# schematic.net
KiCad netlist of a schematic drawn in EAGLE
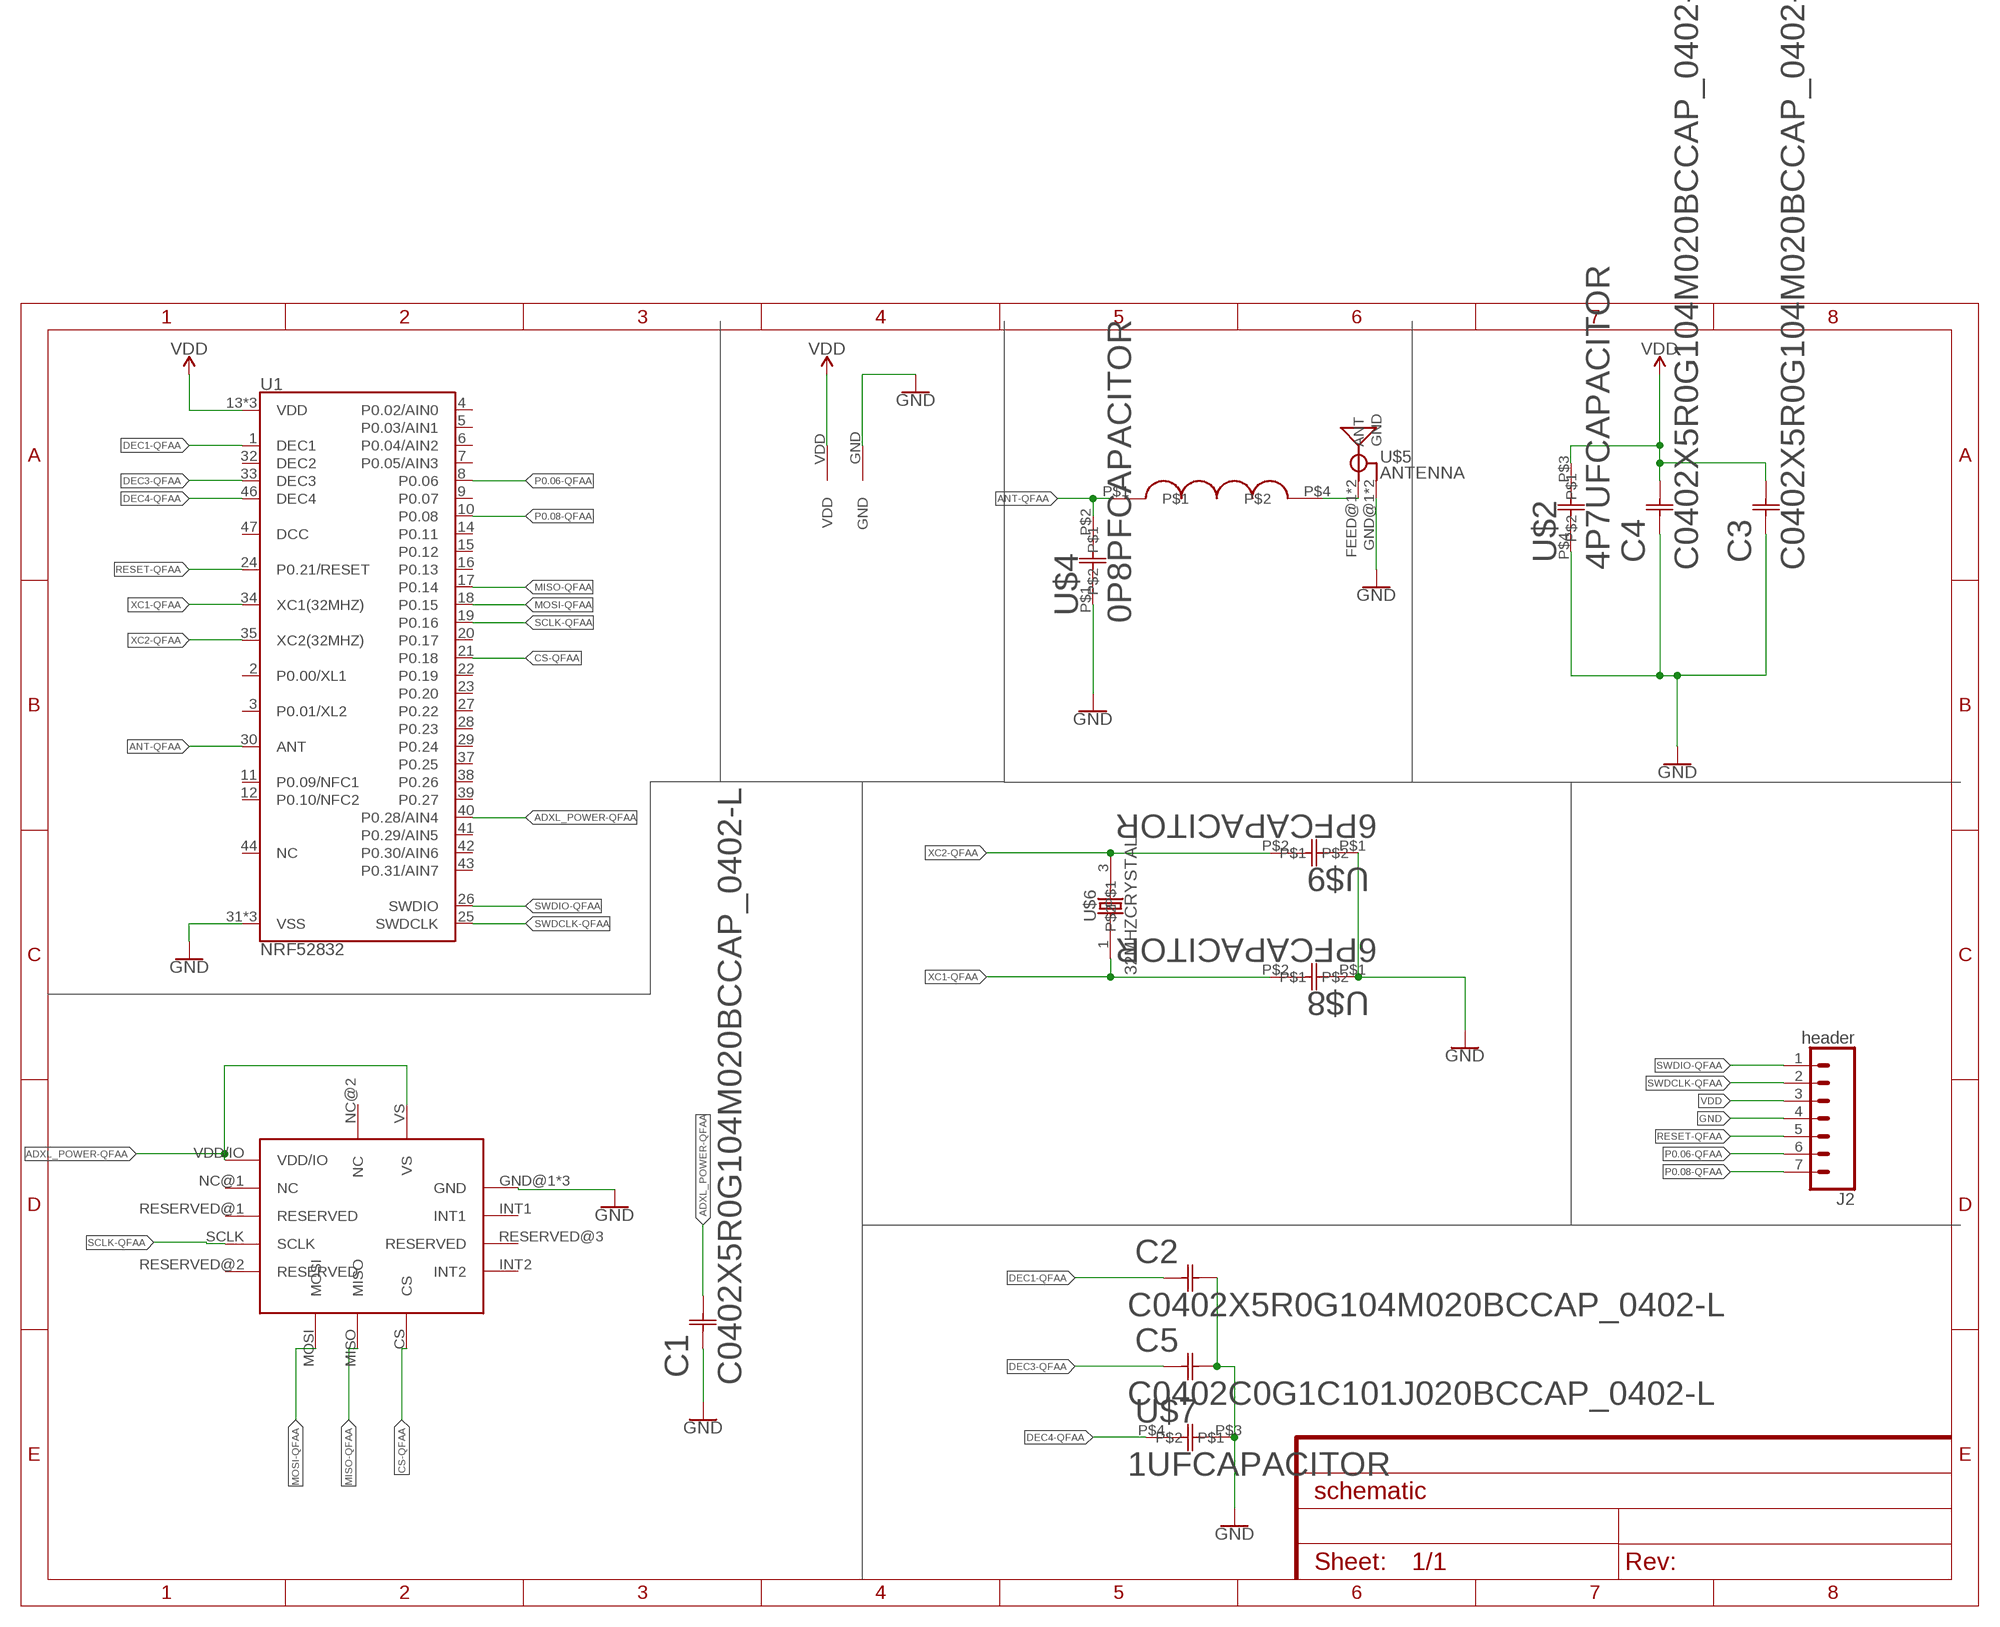
[diagram p0: schematic, sheet 1]

(export (version "E")
  (design (tool "Eeschema 10.0.6"))
  (components
    (comp (ref "C1")
      (value "C0402X5R0G104M020BCCAP_0402-L")
      (footprint "eagle-import:CAP_0402-L")
      (fields (field (name "MANUFACTURER_PART_NUMBER") "C0402C0G1C101J020BC"))
      (libsource (lib "eagle-import") (part "C0402X5R0G104M020BCCAP_0402-L"))
    )
    (comp (ref "C2")
      (value "C0402X5R0G104M020BCCAP_0402-L")
      (footprint "eagle-import:CAP_0402-L")
      (fields (field (name "MANUFACTURER_PART_NUMBER") "C0402C0G1C101J020BC"))
      (libsource (lib "eagle-import") (part "C0402X5R0G104M020BCCAP_0402-L"))
    )
    (comp (ref "C3")
      (value "C0402X5R0G104M020BCCAP_0402-L")
      (footprint "eagle-import:CAP_0402-L")
      (fields (field (name "MANUFACTURER_PART_NUMBER") "C0402C0G1C101J020BC"))
      (libsource (lib "eagle-import") (part "C0402X5R0G104M020BCCAP_0402-L"))
    )
    (comp (ref "C4")
      (value "C0402X5R0G104M020BCCAP_0402-L")
      (footprint "eagle-import:CAP_0402-L")
      (fields (field (name "MANUFACTURER_PART_NUMBER") "C0402C0G1C101J020BC"))
      (libsource (lib "eagle-import") (part "C0402X5R0G104M020BCCAP_0402-L"))
    )
    (comp (ref "C5")
      (value "C0402C0G1C101J020BCCAP_0402-L")
      (footprint "eagle-import:CAP_0402-L")
      (fields (field (name "MANUFACTURER_PART_NUMBER") "C0402C0G1C101J020BC"))
      (libsource (lib "eagle-import") (part "C0402C0G1C101J020BCCAP_0402-L"))
    )
    (comp (ref "J2")
      (value "header")
      (footprint "eagle-import:1X07")
      (libsource (lib "eagle-import") (part "CONN_07"))
    )
    (comp (ref "U$1")
      (value "ADXL362")
      (footprint "eagle-import:TFLGA-16_3.3MMX3.1MM")
      (libsource (lib "eagle-import") (part "ADXL362"))
    )
    (comp (ref "U$2")
      (value "4P7UFCAPACITOR")
      (footprint "eagle-import:4P7UFCAPACITOR")
      (libsource (lib "eagle-import") (part "4P7UFCAPACITOR"))
    )
    (comp (ref "U$3")
      (value "3.9INDUCTOR")
      (footprint "eagle-import:744917039")
      (libsource (lib "eagle-import") (part "3.9INDUCTOR"))
    )
    (comp (ref "U$4")
      (value "0P8PFCAPACITOR")
      (footprint "eagle-import:0P8PFCAPACITOR")
      (libsource (lib "eagle-import") (part "0P8PFCAPACITOR"))
    )
    (comp (ref "U$5")
      (value "ANTENNA")
      (footprint "eagle-import:ANTENNA_FOOTPRINT")
      (libsource (lib "eagle-import") (part "ANTENNA"))
    )
    (comp (ref "U$6")
      (value "32MHZCRYSTAL")
      (footprint "eagle-import:32MHZCRYSTAL")
      (libsource (lib "eagle-import") (part "32MHZCRYSTAL"))
    )
    (comp (ref "U$7")
      (value "1UFCAPACITOR")
      (footprint "eagle-import:1UFCAPACITOR")
      (libsource (lib "eagle-import") (part "1UFCAPACITOR"))
    )
    (comp (ref "U$8")
      (value "6PFCAPACITOR")
      (footprint "eagle-import:6PFCAPACITOR")
      (libsource (lib "eagle-import") (part "6PFCAPACITOR"))
    )
    (comp (ref "U$9")
      (value "6PFCAPACITOR")
      (footprint "eagle-import:6PFCAPACITOR")
      (libsource (lib "eagle-import") (part "6PFCAPACITOR"))
    )
    (comp (ref "U$10")
      (value "POWER")
      (footprint "eagle-import:POWER")
      (libsource (lib "eagle-import") (part "POWER"))
    )
    (comp (ref "U1")
      (value "NRF52832")
      (footprint "eagle-import:QFN48-6X6MM")
      (libsource (lib "eagle-import") (part "NRF52832"))
    )
  )
  (nets
    (net (code "1") (name "ADXL_POWER-QFAA") (class "Default")
      (node (ref "C1") (pin "2") (pinfunction "22_2") (pintype "passive"))
      (node (ref "U$1") (pin "VDD/IO") (pinfunction "VDD/IO_VDD/IO") (pintype "bidirectional"))
      (node (ref "U$1") (pin "VS") (pinfunction "VS_VS") (pintype "bidirectional"))
      (node (ref "U1") (pin "40") (pinfunction "P0.28/AIN4_40") (pintype "bidirectional"))
    )
    (net (code "2") (name "ANT-QFAA") (class "Default")
      (node (ref "U$3") (pin "P$1") (pinfunction "P$1_P$1") (pintype "bidirectional"))
      (node (ref "U$4") (pin "P$2") (pinfunction "P$2_P$2") (pintype "bidirectional"))
      (node (ref "U1") (pin "30") (pinfunction "ANT_30") (pintype "bidirectional"))
    )
    (net (code "3") (name "CS-QFAA") (class "Default")
      (node (ref "U$1") (pin "CS") (pinfunction "CS_CS") (pintype "bidirectional"))
      (node (ref "U1") (pin "21") (pinfunction "P0.18_21") (pintype "bidirectional"))
    )
    (net (code "4") (name "DEC1-QFAA") (class "Default")
      (node (ref "C2") (pin "1") (pinfunction "11_1") (pintype "passive"))
      (node (ref "U1") (pin "1") (pinfunction "DEC1_1") (pintype "bidirectional"))
    )
    (net (code "5") (name "DEC3-QFAA") (class "Default")
      (node (ref "C5") (pin "1") (pinfunction "11_1") (pintype "passive"))
      (node (ref "U1") (pin "33") (pinfunction "DEC3_33") (pintype "bidirectional"))
    )
    (net (code "6") (name "DEC4-QFAA") (class "Default")
      (node (ref "U$7") (pin "P$4") (pinfunction "P$1_P$4") (pintype "bidirectional"))
      (node (ref "U1") (pin "46") (pinfunction "DEC4_46") (pintype "bidirectional"))
    )
    (net (code "7") (name "GND") (class "Default")
      (node (ref "C1") (pin "1") (pinfunction "11_1") (pintype "passive"))
      (node (ref "C2") (pin "2") (pinfunction "22_2") (pintype "passive"))
      (node (ref "C3") (pin "1") (pinfunction "11_1") (pintype "passive"))
      (node (ref "C4") (pin "1") (pinfunction "11_1") (pintype "passive"))
      (node (ref "C5") (pin "2") (pinfunction "22_2") (pintype "passive"))
      (node (ref "J2") (pin "4") (pinfunction "4_4") (pintype "passive"))
      (node (ref "U$1") (pin "GND@1") (pinfunction "GND_GND@1") (pintype "bidirectional"))
      (node (ref "U$1") (pin "GND@2") (pinfunction "GND_GND@2") (pintype "bidirectional"))
      (node (ref "U$1") (pin "GND@3") (pinfunction "GND_GND@3") (pintype "bidirectional"))
      (node (ref "U$10") (pin "GND") (pinfunction "GND_GND") (pintype "bidirectional"))
      (node (ref "U$2") (pin "P$4") (pinfunction "P$1_P$4") (pintype "bidirectional"))
      (node (ref "U$4") (pin "P$1") (pinfunction "P$1_P$1") (pintype "bidirectional"))
      (node (ref "U$5") (pin "GND@1") (pinfunction "GND_GND@1") (pintype "bidirectional"))
      (node (ref "U$5") (pin "GND@2") (pinfunction "GND_GND@2") (pintype "bidirectional"))
      (node (ref "U$7") (pin "P$3") (pinfunction "P$2_P$3") (pintype "bidirectional"))
      (node (ref "U$8") (pin "P$1") (pinfunction "P$1_P$1") (pintype "bidirectional"))
      (node (ref "U$9") (pin "P$1") (pinfunction "P$1_P$1") (pintype "bidirectional"))
      (node (ref "U1") (pin "31") (pinfunction "VSS_31") (pintype "bidirectional"))
      (node (ref "U1") (pin "45") (pinfunction "VSS_45") (pintype "bidirectional"))
      (node (ref "U1") (pin "EP") (pinfunction "VSS_EP") (pintype "bidirectional"))
    )
    (net (code "8") (name "MISO-QFAA") (class "Default")
      (node (ref "U$1") (pin "MISO") (pinfunction "MISO_MISO") (pintype "bidirectional"))
      (node (ref "U1") (pin "17") (pinfunction "P0.14_17") (pintype "bidirectional"))
    )
    (net (code "9") (name "MOSI-QFAA") (class "Default")
      (node (ref "U$1") (pin "MOSI") (pinfunction "MOSI_MOSI") (pintype "bidirectional"))
      (node (ref "U1") (pin "18") (pinfunction "P0.15_18") (pintype "bidirectional"))
    )
    (net (code "10") (name "Net-(U$3-P$2)") (class "Default")
      (node (ref "U$3") (pin "P$4") (pinfunction "P$2_P$4") (pintype "bidirectional"))
      (node (ref "U$5") (pin "FEED@1") (pinfunction "ANT_FEED@1") (pintype "bidirectional"))
      (node (ref "U$5") (pin "FEED@2") (pinfunction "ANT_FEED@2") (pintype "bidirectional"))
    )
    (net (code "11") (name "P0.06-QFAA") (class "Default")
      (node (ref "J2") (pin "6") (pinfunction "6_6") (pintype "passive"))
      (node (ref "U1") (pin "8") (pinfunction "P0.06_8") (pintype "bidirectional"))
    )
    (net (code "12") (name "P0.08-QFAA") (class "Default")
      (node (ref "J2") (pin "7") (pinfunction "7_7") (pintype "passive"))
      (node (ref "U1") (pin "10") (pinfunction "P0.08_10") (pintype "bidirectional"))
    )
    (net (code "13") (name "RESET-QFAA") (class "Default")
      (node (ref "J2") (pin "5") (pinfunction "5_5") (pintype "passive"))
      (node (ref "U1") (pin "24") (pinfunction "P0.21/RESET_24") (pintype "bidirectional"))
    )
    (net (code "14") (name "SCLK-QFAA") (class "Default")
      (node (ref "U$1") (pin "SCLK") (pinfunction "SCLK_SCLK") (pintype "bidirectional"))
      (node (ref "U1") (pin "19") (pinfunction "P0.16_19") (pintype "bidirectional"))
    )
    (net (code "15") (name "SWDCLK-QFAA") (class "Default")
      (node (ref "J2") (pin "2") (pinfunction "2_2") (pintype "passive"))
      (node (ref "U1") (pin "25") (pinfunction "SWDCLK_25") (pintype "bidirectional"))
    )
    (net (code "16") (name "SWDIO-QFAA") (class "Default")
      (node (ref "J2") (pin "1") (pinfunction "1_1") (pintype "passive"))
      (node (ref "U1") (pin "26") (pinfunction "SWDIO_26") (pintype "bidirectional"))
    )
    (net (code "17") (name "VDD") (class "Default")
      (node (ref "C3") (pin "2") (pinfunction "22_2") (pintype "passive"))
      (node (ref "C4") (pin "2") (pinfunction "22_2") (pintype "passive"))
      (node (ref "J2") (pin "3") (pinfunction "3_3") (pintype "passive"))
      (node (ref "U$10") (pin "VDD") (pinfunction "VDD_VDD") (pintype "bidirectional"))
      (node (ref "U$2") (pin "P$3") (pinfunction "P$2_P$3") (pintype "bidirectional"))
      (node (ref "U1") (pin "13") (pinfunction "VDD_13") (pintype "bidirectional"))
      (node (ref "U1") (pin "36") (pinfunction "VDD_36") (pintype "bidirectional"))
      (node (ref "U1") (pin "48") (pinfunction "VDD_48") (pintype "bidirectional"))
    )
    (net (code "18") (name "XC1-QFAA") (class "Default")
      (node (ref "U$6") (pin "1") (pinfunction "P$1_1") (pintype "bidirectional"))
      (node (ref "U$8") (pin "P$2") (pinfunction "P$2_P$2") (pintype "bidirectional"))
      (node (ref "U1") (pin "34") (pinfunction "XC1(32MHZ)_34") (pintype "bidirectional"))
    )
    (net (code "19") (name "XC2-QFAA") (class "Default")
      (node (ref "U$6") (pin "3") (pinfunction "P$2_3") (pintype "bidirectional"))
      (node (ref "U$9") (pin "P$2") (pinfunction "P$2_P$2") (pintype "bidirectional"))
      (node (ref "U1") (pin "35") (pinfunction "XC2(32MHZ)_35") (pintype "bidirectional"))
    )
    (net (code "20") (name "unconnected-(U$1-NC-PadNC@1)") (class "Default")
      (node (ref "U$1") (pin "NC@1") (pinfunction "NC_NC@1") (pintype "bidirectional"))
    )
    (net (code "21") (name "unconnected-(U$1-NC-PadNC@2)") (class "Default")
      (node (ref "U$1") (pin "NC@2") (pinfunction "NC_NC@2") (pintype "bidirectional"))
    )
    (net (code "22") (name "unconnected-(U$1-PadINT1)") (class "Default")
      (node (ref "U$1") (pin "INT1") (pinfunction "INT1_INT1") (pintype "bidirectional"))
    )
    (net (code "23") (name "unconnected-(U$1-PadINT2)") (class "Default")
      (node (ref "U$1") (pin "INT2") (pinfunction "INT2_INT2") (pintype "bidirectional"))
    )
    (net (code "24") (name "unconnected-(U$1-RESERVED-PadRESERVED@1)") (class "Default")
      (node (ref "U$1") (pin "RESERVED@1") (pinfunction "RESERVED_RESERVED@1") (pintype "bidirectional"))
    )
    (net (code "25") (name "unconnected-(U$1-RESERVED-PadRESERVED@2)") (class "Default")
      (node (ref "U$1") (pin "RESERVED@2") (pinfunction "RESERVED_RESERVED@2") (pintype "bidirectional"))
    )
    (net (code "26") (name "unconnected-(U$1-RESERVED-PadRESERVED@3)") (class "Default")
      (node (ref "U$1") (pin "RESERVED@3") (pinfunction "RESERVED_RESERVED@3") (pintype "bidirectional"))
    )
    (net (code "27") (name "unconnected-(U1-DCC-Pad47)") (class "Default")
      (node (ref "U1") (pin "47") (pinfunction "DCC_47") (pintype "bidirectional"))
    )
    (net (code "28") (name "unconnected-(U1-DEC2-Pad32)") (class "Default")
      (node (ref "U1") (pin "32") (pinfunction "DEC2_32") (pintype "bidirectional"))
    )
    (net (code "29") (name "unconnected-(U1-NC-Pad44)") (class "Default")
      (node (ref "U1") (pin "44") (pinfunction "NC_44") (pintype "bidirectional"))
    )
    (net (code "30") (name "unconnected-(U1-P0.00{slash}XL1-Pad2)") (class "Default")
      (node (ref "U1") (pin "2") (pinfunction "P0.00/XL1_2") (pintype "bidirectional"))
    )
    (net (code "31") (name "unconnected-(U1-P0.01{slash}XL2-Pad3)") (class "Default")
      (node (ref "U1") (pin "3") (pinfunction "P0.01/XL2_3") (pintype "bidirectional"))
    )
    (net (code "32") (name "unconnected-(U1-P0.02{slash}AIN0-Pad4)") (class "Default")
      (node (ref "U1") (pin "4") (pinfunction "P0.02/AIN0_4") (pintype "bidirectional"))
    )
    (net (code "33") (name "unconnected-(U1-P0.03{slash}AIN1-Pad5)") (class "Default")
      (node (ref "U1") (pin "5") (pinfunction "P0.03/AIN1_5") (pintype "bidirectional"))
    )
    (net (code "34") (name "unconnected-(U1-P0.04{slash}AIN2-Pad6)") (class "Default")
      (node (ref "U1") (pin "6") (pinfunction "P0.04/AIN2_6") (pintype "bidirectional"))
    )
    (net (code "35") (name "unconnected-(U1-P0.05{slash}AIN3-Pad7)") (class "Default")
      (node (ref "U1") (pin "7") (pinfunction "P0.05/AIN3_7") (pintype "bidirectional"))
    )
    (net (code "36") (name "unconnected-(U1-P0.07-Pad9)") (class "Default")
      (node (ref "U1") (pin "9") (pinfunction "P0.07_9") (pintype "bidirectional"))
    )
    (net (code "37") (name "unconnected-(U1-P0.09{slash}NFC1-Pad11)") (class "Default")
      (node (ref "U1") (pin "11") (pinfunction "P0.09/NFC1_11") (pintype "bidirectional"))
    )
    (net (code "38") (name "unconnected-(U1-P0.10{slash}NFC2-Pad12)") (class "Default")
      (node (ref "U1") (pin "12") (pinfunction "P0.10/NFC2_12") (pintype "bidirectional"))
    )
    (net (code "39") (name "unconnected-(U1-P0.11-Pad14)") (class "Default")
      (node (ref "U1") (pin "14") (pinfunction "P0.11_14") (pintype "bidirectional"))
    )
    (net (code "40") (name "unconnected-(U1-P0.12-Pad15)") (class "Default")
      (node (ref "U1") (pin "15") (pinfunction "P0.12_15") (pintype "bidirectional"))
    )
    (net (code "41") (name "unconnected-(U1-P0.13-Pad16)") (class "Default")
      (node (ref "U1") (pin "16") (pinfunction "P0.13_16") (pintype "bidirectional"))
    )
    (net (code "42") (name "unconnected-(U1-P0.17-Pad20)") (class "Default")
      (node (ref "U1") (pin "20") (pinfunction "P0.17_20") (pintype "bidirectional"))
    )
    (net (code "43") (name "unconnected-(U1-P0.19-Pad22)") (class "Default")
      (node (ref "U1") (pin "22") (pinfunction "P0.19_22") (pintype "bidirectional"))
    )
    (net (code "44") (name "unconnected-(U1-P0.20-Pad23)") (class "Default")
      (node (ref "U1") (pin "23") (pinfunction "P0.20_23") (pintype "bidirectional"))
    )
    (net (code "45") (name "unconnected-(U1-P0.22-Pad27)") (class "Default")
      (node (ref "U1") (pin "27") (pinfunction "P0.22_27") (pintype "bidirectional"))
    )
    (net (code "46") (name "unconnected-(U1-P0.23-Pad28)") (class "Default")
      (node (ref "U1") (pin "28") (pinfunction "P0.23_28") (pintype "bidirectional"))
    )
    (net (code "47") (name "unconnected-(U1-P0.24-Pad29)") (class "Default")
      (node (ref "U1") (pin "29") (pinfunction "P0.24_29") (pintype "bidirectional"))
    )
    (net (code "48") (name "unconnected-(U1-P0.25-Pad37)") (class "Default")
      (node (ref "U1") (pin "37") (pinfunction "P0.25_37") (pintype "bidirectional"))
    )
    (net (code "49") (name "unconnected-(U1-P0.26-Pad38)") (class "Default")
      (node (ref "U1") (pin "38") (pinfunction "P0.26_38") (pintype "bidirectional"))
    )
    (net (code "50") (name "unconnected-(U1-P0.27-Pad39)") (class "Default")
      (node (ref "U1") (pin "39") (pinfunction "P0.27_39") (pintype "bidirectional"))
    )
    (net (code "51") (name "unconnected-(U1-P0.29{slash}AIN5-Pad41)") (class "Default")
      (node (ref "U1") (pin "41") (pinfunction "P0.29/AIN5_41") (pintype "bidirectional"))
    )
    (net (code "52") (name "unconnected-(U1-P0.30{slash}AIN6-Pad42)") (class "Default")
      (node (ref "U1") (pin "42") (pinfunction "P0.30/AIN6_42") (pintype "bidirectional"))
    )
    (net (code "53") (name "unconnected-(U1-P0.31{slash}AIN7-Pad43)") (class "Default")
      (node (ref "U1") (pin "43") (pinfunction "P0.31/AIN7_43") (pintype "bidirectional"))
    )
  )
)
